# rc2014_romram.net
KiCad netlist of a schematic drawn in EAGLE
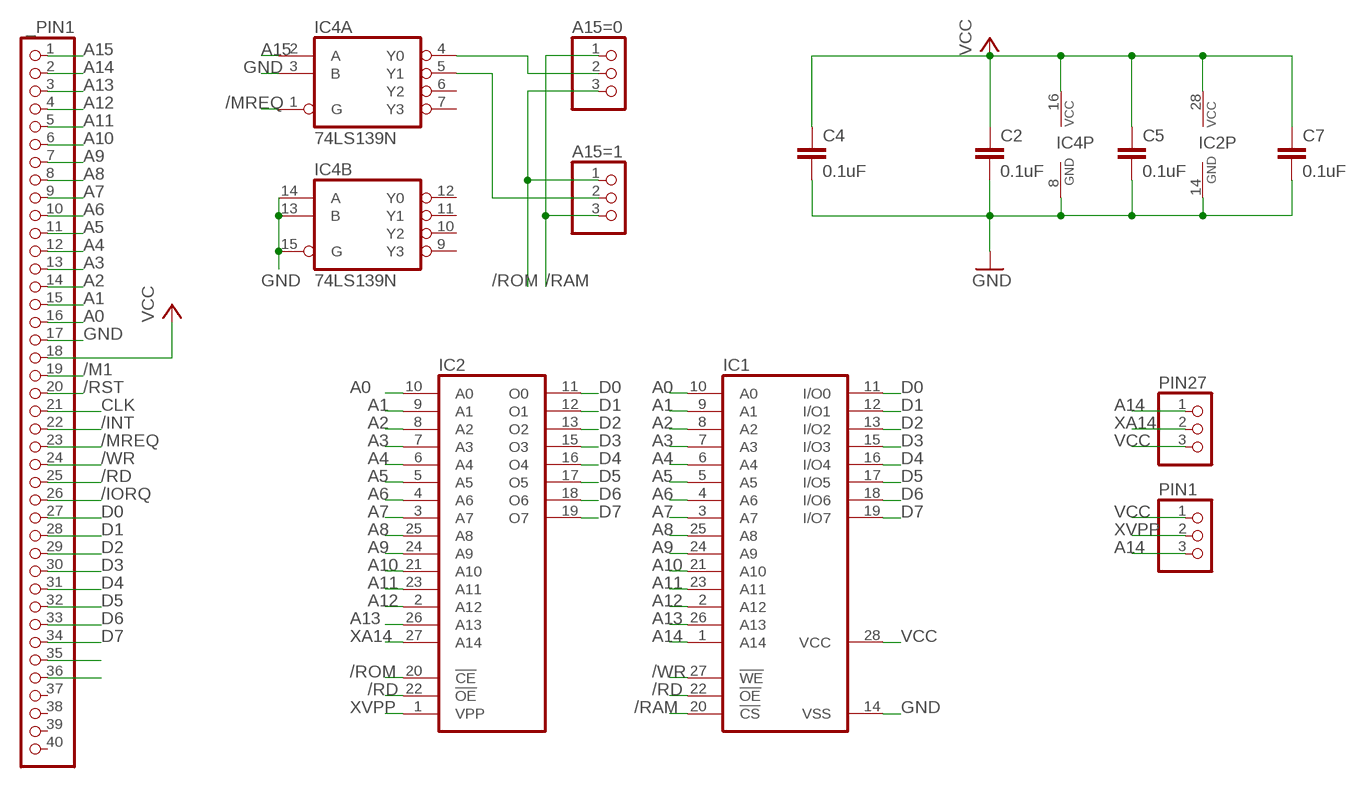
[diagram p0: schematic, sheet 1]

(export (version "E")
  (design (tool "Eeschema 10.0.6"))
  (components
    (comp (ref "A15=0")
      (value "PINHD-1X3")
      (footprint "eagle-import:1X03")
      (libsource (lib "eagle-import") (part "PINHD-1X3"))
    )
    (comp (ref "A15=1")
      (value "PINHD-1X3")
      (footprint "eagle-import:1X03")
      (libsource (lib "eagle-import") (part "PINHD-1X3"))
    )
    (comp (ref "C2")
      (value "0.1uF")
      (footprint "eagle-import:C050-024X044")
      (libsource (lib "eagle-import") (part "C-EU050-024X044"))
    )
    (comp (ref "C4")
      (value "0.1uF")
      (footprint "eagle-import:C050-024X044")
      (libsource (lib "eagle-import") (part "C-EU050-024X044"))
    )
    (comp (ref "C5")
      (value "0.1uF")
      (footprint "eagle-import:C050-024X044")
      (libsource (lib "eagle-import") (part "C-EU050-024X044"))
    )
    (comp (ref "C7")
      (value "0.1uF")
      (footprint "eagle-import:C050-024X044")
      (libsource (lib "eagle-import") (part "C-EU050-024X044"))
    )
    (comp (ref "IC1")
      (value "62256P")
      (footprint "eagle-import:DIL28-6")
      (libsource (lib "eagle-import") (part "62256P"))
    )
    (comp (ref "IC2")
      (value "27256")
      (footprint "eagle-import:DIL28")
      (libsource (lib "eagle-import") (part "27256"))
    )
    (comp (ref "IC4")
      (value "74LS139N")
      (footprint "eagle-import:DIL16")
      (libsource (lib "eagle-import") (part "74139NLS"))
    )
    (comp (ref "PIN1")
      (value "PINHD-1X3")
      (footprint "eagle-import:1X03")
      (libsource (lib "eagle-import") (part "PINHD-1X3"))
    )
    (comp (ref "PIN27")
      (value "PINHD-1X3")
      (footprint "eagle-import:1X03")
      (libsource (lib "eagle-import") (part "PINHD-1X3"))
    )
    (comp (ref "_PIN1")
      (value "PINHD-1X40")
      (footprint "eagle-import:1X40")
      (libsource (lib "eagle-import") (part "PINHD-1X40"))
    )
  )
  (nets
    (net (code "1") (name "/A0") (class "Default")
      (node (ref "IC1") (pin "10") (pinfunction "A0_10") (pintype "input"))
      (node (ref "IC2") (pin "10") (pinfunction "A0_10") (pintype "input"))
      (node (ref "_PIN1") (pin "16") (pinfunction "16_16") (pintype "passive"))
    )
    (net (code "2") (name "/A1") (class "Default")
      (node (ref "IC1") (pin "9") (pinfunction "A1_9") (pintype "input"))
      (node (ref "IC2") (pin "9") (pinfunction "A1_9") (pintype "input"))
      (node (ref "_PIN1") (pin "15") (pinfunction "15_15") (pintype "passive"))
    )
    (net (code "3") (name "/A2") (class "Default")
      (node (ref "IC1") (pin "8") (pinfunction "A2_8") (pintype "input"))
      (node (ref "IC2") (pin "8") (pinfunction "A2_8") (pintype "input"))
      (node (ref "_PIN1") (pin "14") (pinfunction "14_14") (pintype "passive"))
    )
    (net (code "4") (name "/A3") (class "Default")
      (node (ref "IC1") (pin "7") (pinfunction "A3_7") (pintype "input"))
      (node (ref "IC2") (pin "7") (pinfunction "A3_7") (pintype "input"))
      (node (ref "_PIN1") (pin "13") (pinfunction "13_13") (pintype "passive"))
    )
    (net (code "5") (name "/A4") (class "Default")
      (node (ref "IC1") (pin "6") (pinfunction "A4_6") (pintype "input"))
      (node (ref "IC2") (pin "6") (pinfunction "A4_6") (pintype "input"))
      (node (ref "_PIN1") (pin "12") (pinfunction "12_12") (pintype "passive"))
    )
    (net (code "6") (name "/A5") (class "Default")
      (node (ref "IC1") (pin "5") (pinfunction "A5_5") (pintype "input"))
      (node (ref "IC2") (pin "5") (pinfunction "A5_5") (pintype "input"))
      (node (ref "_PIN1") (pin "11") (pinfunction "11_11") (pintype "passive"))
    )
    (net (code "7") (name "/A6") (class "Default")
      (node (ref "IC1") (pin "4") (pinfunction "A6_4") (pintype "input"))
      (node (ref "IC2") (pin "4") (pinfunction "A6_4") (pintype "input"))
      (node (ref "_PIN1") (pin "10") (pinfunction "10_10") (pintype "passive"))
    )
    (net (code "8") (name "/A7") (class "Default")
      (node (ref "IC1") (pin "3") (pinfunction "A7_3") (pintype "input"))
      (node (ref "IC2") (pin "3") (pinfunction "A7_3") (pintype "input"))
      (node (ref "_PIN1") (pin "9") (pinfunction "9_9") (pintype "passive"))
    )
    (net (code "9") (name "/A8") (class "Default")
      (node (ref "IC1") (pin "25") (pinfunction "A8_25") (pintype "input"))
      (node (ref "IC2") (pin "25") (pinfunction "A8_25") (pintype "input"))
      (node (ref "_PIN1") (pin "8") (pinfunction "8_8") (pintype "passive"))
    )
    (net (code "10") (name "/A9") (class "Default")
      (node (ref "IC1") (pin "24") (pinfunction "A9_24") (pintype "input"))
      (node (ref "IC2") (pin "24") (pinfunction "A9_24") (pintype "input"))
      (node (ref "_PIN1") (pin "7") (pinfunction "7_7") (pintype "passive"))
    )
    (net (code "11") (name "/A10") (class "Default")
      (node (ref "IC1") (pin "21") (pinfunction "A10_21") (pintype "input"))
      (node (ref "IC2") (pin "21") (pinfunction "A10_21") (pintype "input"))
      (node (ref "_PIN1") (pin "6") (pinfunction "6_6") (pintype "passive"))
    )
    (net (code "12") (name "/A11") (class "Default")
      (node (ref "IC1") (pin "23") (pinfunction "A11_23") (pintype "input"))
      (node (ref "IC2") (pin "23") (pinfunction "A11_23") (pintype "input"))
      (node (ref "_PIN1") (pin "5") (pinfunction "5_5") (pintype "passive"))
    )
    (net (code "13") (name "/A12") (class "Default")
      (node (ref "IC1") (pin "2") (pinfunction "A12_2") (pintype "input"))
      (node (ref "IC2") (pin "2") (pinfunction "A12_2") (pintype "input"))
      (node (ref "_PIN1") (pin "4") (pinfunction "4_4") (pintype "passive"))
    )
    (net (code "14") (name "/A13") (class "Default")
      (node (ref "IC1") (pin "26") (pinfunction "A13_26") (pintype "input"))
      (node (ref "IC2") (pin "26") (pinfunction "A13_26") (pintype "input"))
      (node (ref "_PIN1") (pin "3") (pinfunction "3_3") (pintype "passive"))
    )
    (net (code "15") (name "/A14") (class "Default")
      (node (ref "IC1") (pin "1") (pinfunction "A14_1") (pintype "input"))
      (node (ref "PIN1") (pin "3") (pinfunction "3_3") (pintype "passive"))
      (node (ref "PIN27") (pin "1") (pinfunction "1_1") (pintype "passive"))
      (node (ref "_PIN1") (pin "2") (pinfunction "2_2") (pintype "passive"))
    )
    (net (code "16") (name "/A15") (class "Default")
      (node (ref "IC4") (pin "2") (pinfunction "A_2") (pintype "input"))
      (node (ref "_PIN1") (pin "1") (pinfunction "1_1") (pintype "passive"))
    )
    (net (code "17") (name "/CLK") (class "Default")
      (node (ref "_PIN1") (pin "21") (pinfunction "21_21") (pintype "passive"))
    )
    (net (code "18") (name "/D0") (class "Default")
      (node (ref "IC1") (pin "11") (pinfunction "I/O0_11") (pintype "bidirectional"))
      (node (ref "IC2") (pin "11") (pinfunction "O0_11") (pintype "tri_state"))
      (node (ref "_PIN1") (pin "27") (pinfunction "27_27") (pintype "passive"))
    )
    (net (code "19") (name "/D1") (class "Default")
      (node (ref "IC1") (pin "12") (pinfunction "I/O1_12") (pintype "bidirectional"))
      (node (ref "IC2") (pin "12") (pinfunction "O1_12") (pintype "tri_state"))
      (node (ref "_PIN1") (pin "28") (pinfunction "28_28") (pintype "passive"))
    )
    (net (code "20") (name "/D2") (class "Default")
      (node (ref "IC1") (pin "13") (pinfunction "I/O2_13") (pintype "bidirectional"))
      (node (ref "IC2") (pin "13") (pinfunction "O2_13") (pintype "tri_state"))
      (node (ref "_PIN1") (pin "29") (pinfunction "29_29") (pintype "passive"))
    )
    (net (code "21") (name "/D3") (class "Default")
      (node (ref "IC1") (pin "15") (pinfunction "I/O3_15") (pintype "bidirectional"))
      (node (ref "IC2") (pin "15") (pinfunction "O3_15") (pintype "tri_state"))
      (node (ref "_PIN1") (pin "30") (pinfunction "30_30") (pintype "passive"))
    )
    (net (code "22") (name "/D4") (class "Default")
      (node (ref "IC1") (pin "16") (pinfunction "I/O4_16") (pintype "bidirectional"))
      (node (ref "IC2") (pin "16") (pinfunction "O4_16") (pintype "tri_state"))
      (node (ref "_PIN1") (pin "31") (pinfunction "31_31") (pintype "passive"))
    )
    (net (code "23") (name "/D5") (class "Default")
      (node (ref "IC1") (pin "17") (pinfunction "I/O5_17") (pintype "bidirectional"))
      (node (ref "IC2") (pin "17") (pinfunction "O5_17") (pintype "tri_state"))
      (node (ref "_PIN1") (pin "32") (pinfunction "32_32") (pintype "passive"))
    )
    (net (code "24") (name "/D6") (class "Default")
      (node (ref "IC1") (pin "18") (pinfunction "I/O6_18") (pintype "bidirectional"))
      (node (ref "IC2") (pin "18") (pinfunction "O6_18") (pintype "tri_state"))
      (node (ref "_PIN1") (pin "33") (pinfunction "33_33") (pintype "passive"))
    )
    (net (code "25") (name "/D7") (class "Default")
      (node (ref "IC1") (pin "19") (pinfunction "I/O7_19") (pintype "bidirectional"))
      (node (ref "IC2") (pin "19") (pinfunction "O7_19") (pintype "tri_state"))
      (node (ref "_PIN1") (pin "34") (pinfunction "34_34") (pintype "passive"))
    )
    (net (code "26") (name "/XA14") (class "Default")
      (node (ref "IC2") (pin "27") (pinfunction "A14_27") (pintype "input"))
      (node (ref "PIN27") (pin "2") (pinfunction "2_2") (pintype "passive"))
    )
    (net (code "27") (name "/XVPP") (class "Default")
      (node (ref "IC2") (pin "1") (pinfunction "VPP_1") (pintype "input"))
      (node (ref "PIN1") (pin "2") (pinfunction "2_2") (pintype "passive"))
    )
    (net (code "28") (name "/{slash}INT") (class "Default")
      (node (ref "_PIN1") (pin "22") (pinfunction "22_22") (pintype "passive"))
    )
    (net (code "29") (name "/{slash}IORQ") (class "Default")
      (node (ref "_PIN1") (pin "26") (pinfunction "26_26") (pintype "passive"))
    )
    (net (code "30") (name "/{slash}M1") (class "Default")
      (node (ref "_PIN1") (pin "19") (pinfunction "19_19") (pintype "passive"))
    )
    (net (code "31") (name "/{slash}MREQ") (class "Default")
      (node (ref "IC4") (pin "1") (pinfunction "G_1") (pintype "input"))
      (node (ref "_PIN1") (pin "23") (pinfunction "23_23") (pintype "passive"))
    )
    (net (code "32") (name "/{slash}RAM") (class "Default")
      (node (ref "A15=0") (pin "1") (pinfunction "1_1") (pintype "passive"))
      (node (ref "A15=1") (pin "3") (pinfunction "3_3") (pintype "passive"))
      (node (ref "IC1") (pin "20") (pinfunction "~{CS}_20") (pintype "input"))
    )
    (net (code "33") (name "/{slash}RD") (class "Default")
      (node (ref "IC1") (pin "22") (pinfunction "~{OE}_22") (pintype "input"))
      (node (ref "IC2") (pin "22") (pinfunction "~{OE}_22") (pintype "input"))
      (node (ref "_PIN1") (pin "25") (pinfunction "25_25") (pintype "passive"))
    )
    (net (code "34") (name "/{slash}ROM") (class "Default")
      (node (ref "A15=0") (pin "3") (pinfunction "3_3") (pintype "passive"))
      (node (ref "A15=1") (pin "1") (pinfunction "1_1") (pintype "passive"))
      (node (ref "IC2") (pin "20") (pinfunction "~{CE}_20") (pintype "input"))
    )
    (net (code "35") (name "/{slash}RST") (class "Default")
      (node (ref "_PIN1") (pin "20") (pinfunction "20_20") (pintype "passive"))
    )
    (net (code "36") (name "/{slash}WR") (class "Default")
      (node (ref "IC1") (pin "27") (pinfunction "~{WE}_27") (pintype "input"))
      (node (ref "_PIN1") (pin "24") (pinfunction "24_24") (pintype "passive"))
    )
    (net (code "37") (name "GND") (class "Default")
      (node (ref "C2") (pin "2") (pinfunction "2_2") (pintype "passive"))
      (node (ref "C4") (pin "2") (pinfunction "2_2") (pintype "passive"))
      (node (ref "C5") (pin "2") (pinfunction "2_2") (pintype "passive"))
      (node (ref "C7") (pin "2") (pinfunction "2_2") (pintype "passive"))
      (node (ref "IC1") (pin "14") (pinfunction "VSS_14") (pintype "power_in"))
      (node (ref "IC2") (pin "14") (pinfunction "GND_14") (pintype "power_in"))
      (node (ref "IC4") (pin "13") (pinfunction "B_13") (pintype "input"))
      (node (ref "IC4") (pin "14") (pinfunction "A_14") (pintype "input"))
      (node (ref "IC4") (pin "15") (pinfunction "G_15") (pintype "input"))
      (node (ref "IC4") (pin "3") (pinfunction "B_3") (pintype "input"))
      (node (ref "IC4") (pin "8") (pinfunction "GND_8") (pintype "power_in"))
      (node (ref "_PIN1") (pin "17") (pinfunction "17_17") (pintype "passive"))
    )
    (net (code "38") (name "Net-(IC4A-Y0)") (class "Default")
      (node (ref "A15=0") (pin "2") (pinfunction "2_2") (pintype "passive"))
      (node (ref "IC4") (pin "4") (pinfunction "Y0_4") (pintype "output"))
    )
    (net (code "39") (name "Net-(IC4A-Y1)") (class "Default")
      (node (ref "A15=1") (pin "2") (pinfunction "2_2") (pintype "passive"))
      (node (ref "IC4") (pin "5") (pinfunction "Y1_5") (pintype "output"))
    )
    (net (code "40") (name "VCC") (class "Default")
      (node (ref "C2") (pin "1") (pinfunction "1_1") (pintype "passive"))
      (node (ref "C4") (pin "1") (pinfunction "1_1") (pintype "passive"))
      (node (ref "C5") (pin "1") (pinfunction "1_1") (pintype "passive"))
      (node (ref "C7") (pin "1") (pinfunction "1_1") (pintype "passive"))
      (node (ref "IC1") (pin "28") (pinfunction "VCC_28") (pintype "power_in"))
      (node (ref "IC2") (pin "28") (pinfunction "VCC_28") (pintype "power_in"))
      (node (ref "IC4") (pin "16") (pinfunction "VCC_16") (pintype "power_in"))
      (node (ref "PIN1") (pin "1") (pinfunction "1_1") (pintype "passive"))
      (node (ref "PIN27") (pin "3") (pinfunction "3_3") (pintype "passive"))
      (node (ref "_PIN1") (pin "18") (pinfunction "18_18") (pintype "passive"))
    )
    (net (code "41") (name "unconnected-(IC4A-Y2-Pad6)") (class "Default")
      (node (ref "IC4") (pin "6") (pinfunction "Y2_6") (pintype "output"))
    )
    (net (code "42") (name "unconnected-(IC4A-Y3-Pad7)") (class "Default")
      (node (ref "IC4") (pin "7") (pinfunction "Y3_7") (pintype "output"))
    )
    (net (code "43") (name "unconnected-(IC4B-Y0-Pad12)") (class "Default")
      (node (ref "IC4") (pin "12") (pinfunction "Y0_12") (pintype "output"))
    )
    (net (code "44") (name "unconnected-(IC4B-Y1-Pad11)") (class "Default")
      (node (ref "IC4") (pin "11") (pinfunction "Y1_11") (pintype "output"))
    )
    (net (code "45") (name "unconnected-(IC4B-Y2-Pad10)") (class "Default")
      (node (ref "IC4") (pin "10") (pinfunction "Y2_10") (pintype "output"))
    )
    (net (code "46") (name "unconnected-(IC4B-Y3-Pad9)") (class "Default")
      (node (ref "IC4") (pin "9") (pinfunction "Y3_9") (pintype "output"))
    )
    (net (code "47") (name "unconnected-(_PIN1-Pad35)") (class "Default")
      (node (ref "_PIN1") (pin "35") (pinfunction "35_35") (pintype "passive"))
    )
    (net (code "48") (name "unconnected-(_PIN1-Pad36)") (class "Default")
      (node (ref "_PIN1") (pin "36") (pinfunction "36_36") (pintype "passive"))
    )
    (net (code "49") (name "unconnected-(_PIN1-Pad37)") (class "Default")
      (node (ref "_PIN1") (pin "37") (pinfunction "37_37") (pintype "passive"))
    )
    (net (code "50") (name "unconnected-(_PIN1-Pad38)") (class "Default")
      (node (ref "_PIN1") (pin "38") (pinfunction "38_38") (pintype "passive"))
    )
    (net (code "51") (name "unconnected-(_PIN1-Pad39)") (class "Default")
      (node (ref "_PIN1") (pin "39") (pinfunction "39_39") (pintype "passive"))
    )
    (net (code "52") (name "unconnected-(_PIN1-Pad40)") (class "Default")
      (node (ref "_PIN1") (pin "40") (pinfunction "40_40") (pintype "passive"))
    )
  )
)
